# EMG_schemqtic.net
KiCad netlist of a schematic drawn in Altium Designer
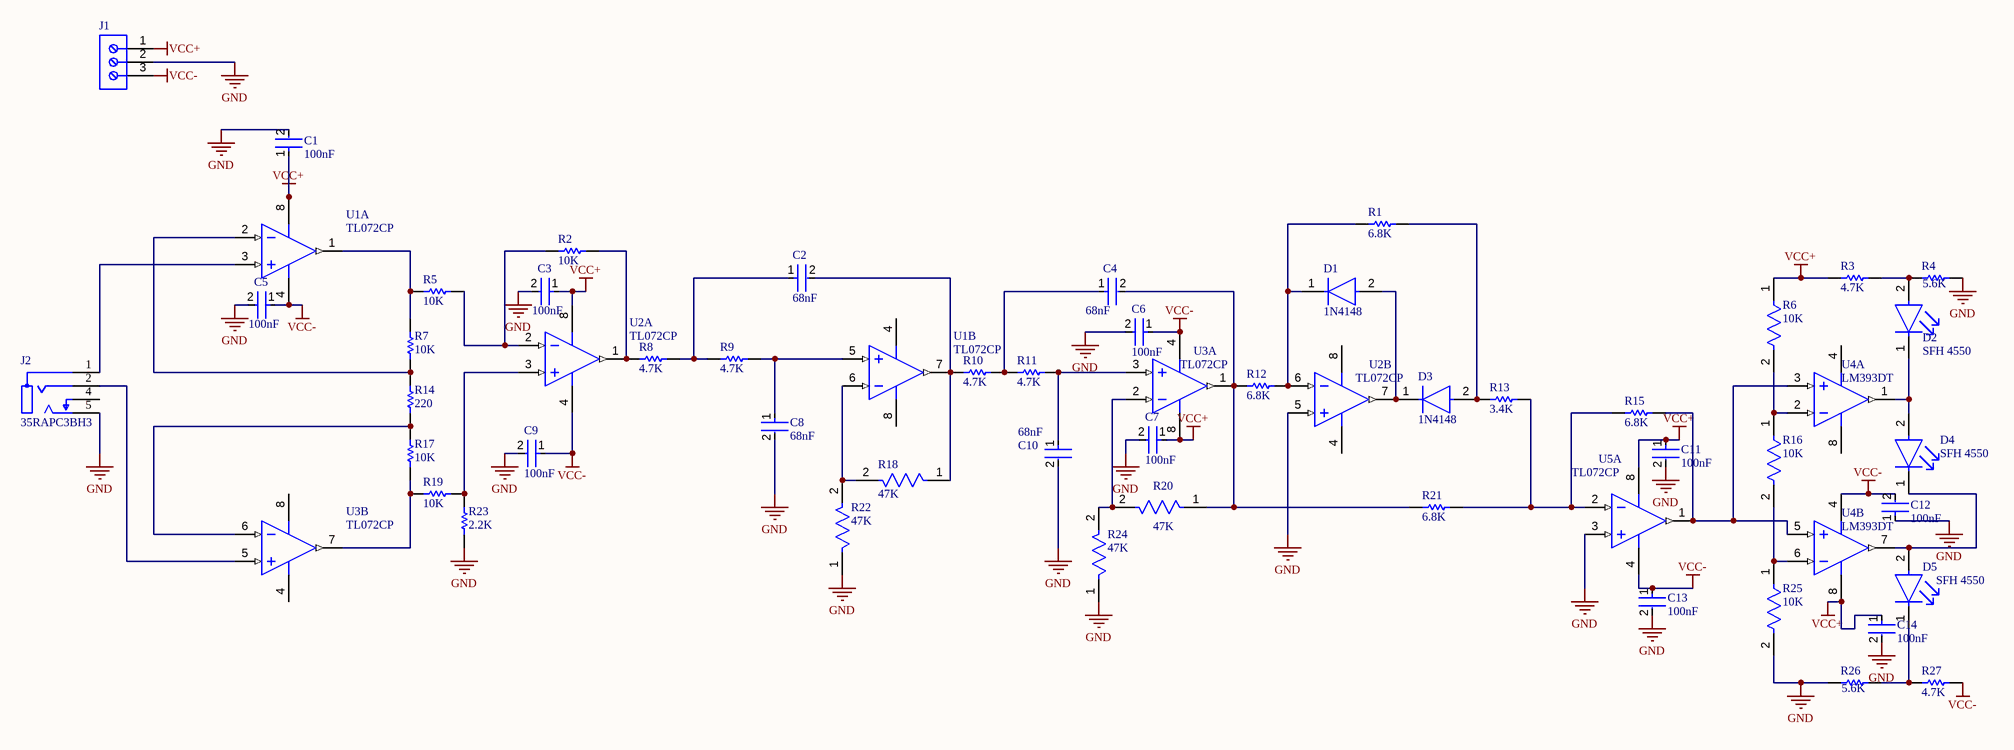
[diagram p0: EMG_schemqtic.SchDoc]

(export (version "E")
  (design (tool "Eeschema 10.0.6"))
  (components
    (comp (ref "C1")
      (value "100nF")
      (footprint "FP-CGA3E-0_3-0_1-IPC_A")
      (description "Cap Ceramic 100nF 50V X7R 10% Pad SMD 0603 +125°C Automotive T/R")
      (fields (field (name "TOLERANCE") "10%") (field (name "VOLTAGE") "50V"))
      (libsource (lib "Altium Content Vault") (part "b4654b650e69147ec39a6b967a45e02"))
    )
    (comp (ref "C2")
      (value "68nF")
      (footprint "FP-1206-L_3_2_0_2-W_1_6_0-IPC_A")
      (description "General Purpose Ceramic Capacitor, 1206, 68nF, 10%, X7R, 15%, 100V")
      (fields (field (name "VOLTAGE") "100V") (field (name "TOLERANCE") "10%"))
      (libsource (lib "Altium Content Vault") (part "02cd4be3c70576c341d710602a673aa"))
    )
    (comp (ref "C3")
      (value "100nF")
      (footprint "FP-CGA3E-0_3-0_1-IPC_A")
      (description "Cap Ceramic 100nF 50V X7R 10% Pad SMD 0603 +125°C Automotive T/R")
      (fields (field (name "TOLERANCE") "10%") (field (name "VOLTAGE") "50V"))
      (libsource (lib "Altium Content Vault") (part "b4654b650e69147ec39a6b967a45e02"))
    )
    (comp (ref "C4")
      (value "68nF")
      (footprint "FP-1206-L_3_2_0_2-W_1_6_0-IPC_A")
      (description "General Purpose Ceramic Capacitor, 1206, 68nF, 10%, X7R, 15%, 100V")
      (fields (field (name "VOLTAGE") "100V") (field (name "TOLERANCE") "10%"))
      (libsource (lib "Altium Content Vault") (part "02cd4be3c70576c341d710602a673aa"))
    )
    (comp (ref "C5")
      (value "100nF")
      (footprint "FP-CGA3E-0_3-0_1-IPC_A")
      (description "Cap Ceramic 100nF 50V X7R 10% Pad SMD 0603 +125°C Automotive T/R")
      (fields (field (name "TOLERANCE") "10%") (field (name "VOLTAGE") "50V"))
      (libsource (lib "Altium Content Vault") (part "b4654b650e69147ec39a6b967a45e02"))
    )
    (comp (ref "C6")
      (value "100nF")
      (footprint "FP-CGA3E-0_3-0_1-IPC_A")
      (description "Cap Ceramic 100nF 50V X7R 10% Pad SMD 0603 +125°C Automotive T/R")
      (fields (field (name "TOLERANCE") "10%") (field (name "VOLTAGE") "50V"))
      (libsource (lib "Altium Content Vault") (part "b4654b650e69147ec39a6b967a45e02"))
    )
    (comp (ref "C7")
      (value "100nF")
      (footprint "FP-CGA3E-0_3-0_1-IPC_A")
      (description "Cap Ceramic 100nF 50V X7R 10% Pad SMD 0603 +125°C Automotive T/R")
      (fields (field (name "TOLERANCE") "10%") (field (name "VOLTAGE") "50V"))
      (libsource (lib "Altium Content Vault") (part "b4654b650e69147ec39a6b967a45e02"))
    )
    (comp (ref "C8")
      (value "68nF")
      (footprint "FP-1206-L_3_2_0_2-W_1_6_0-IPC_A")
      (description "General Purpose Ceramic Capacitor, 1206, 68nF, 10%, X7R, 15%, 100V")
      (fields (field (name "VOLTAGE") "100V") (field (name "TOLERANCE") "10%"))
      (libsource (lib "Altium Content Vault") (part "02cd4be3c70576c341d710602a673aa"))
    )
    (comp (ref "C9")
      (value "100nF")
      (footprint "FP-CGA3E-0_3-0_1-IPC_A")
      (description "Cap Ceramic 100nF 50V X7R 10% Pad SMD 0603 +125°C Automotive T/R")
      (fields (field (name "TOLERANCE") "10%") (field (name "VOLTAGE") "50V"))
      (libsource (lib "Altium Content Vault") (part "b4654b650e69147ec39a6b967a45e02"))
    )
    (comp (ref "C10")
      (value "68nF")
      (footprint "FP-1206-L_3_2_0_2-W_1_6_0-IPC_A")
      (description "General Purpose Ceramic Capacitor, 1206, 68nF, 10%, X7R, 15%, 100V")
      (fields (field (name "VOLTAGE") "100V") (field (name "TOLERANCE") "10%"))
      (libsource (lib "Altium Content Vault") (part "02cd4be3c70576c341d710602a673aa"))
    )
    (comp (ref "C11")
      (value "100nF")
      (footprint "FP-CGA3E-0_3-0_1-IPC_A")
      (description "Cap Ceramic 100nF 50V X7R 10% Pad SMD 0603 +125°C Automotive T/R")
      (fields (field (name "TOLERANCE") "10%") (field (name "VOLTAGE") "50V"))
      (libsource (lib "Altium Content Vault") (part "b4654b650e69147ec39a6b967a45e02"))
    )
    (comp (ref "C12")
      (value "100nF")
      (footprint "FP-CGA3E-0_3-0_1-IPC_A")
      (description "Cap Ceramic 100nF 50V X7R 10% Pad SMD 0603 +125°C Automotive T/R")
      (fields (field (name "TOLERANCE") "10%") (field (name "VOLTAGE") "50V"))
      (libsource (lib "Altium Content Vault") (part "b4654b650e69147ec39a6b967a45e02"))
    )
    (comp (ref "C13")
      (value "100nF")
      (footprint "FP-CGA3E-0_3-0_1-IPC_A")
      (description "Cap Ceramic 100nF 50V X7R 10% Pad SMD 0603 +125°C Automotive T/R")
      (fields (field (name "TOLERANCE") "10%") (field (name "VOLTAGE") "50V"))
      (libsource (lib "Altium Content Vault") (part "b4654b650e69147ec39a6b967a45e02"))
    )
    (comp (ref "C14")
      (value "100nF")
      (footprint "FP-CGA3E-0_3-0_1-IPC_A")
      (description "Cap Ceramic 100nF 50V X7R 10% Pad SMD 0603 +125°C Automotive T/R")
      (fields (field (name "TOLERANCE") "10%") (field (name "VOLTAGE") "50V"))
      (libsource (lib "Altium Content Vault") (part "b4654b650e69147ec39a6b967a45e02"))
    )
    (comp (ref "D1")
      (value "1N4148")
      (footprint "FP-017AG-MFG")
      (description "DIODE GEN PURP 100V 200MA DO35")
      (fields (field (name "VOLTAGE") "100V"))
      (libsource (lib "Altium Content Vault") (part "d7152d700b627762746794eb795d46e"))
    )
    (comp (ref "D2")
      (value "SFH 4550")
      (footprint "FP-SFH_4550-MFG")
      (description "EMITTER IR 860NM 100MA RADIAL")
      (fields
        (field (name "OCTOPART") "https://octopart.com/sfh+4550-osram+opto-55410894")
        (field (name "MANUFACTURER") "Osram Opto")
      )
      (libsource (lib "Altium Content Vault") (part "75a0115997dd6a71327e26aab64f6f8"))
    )
    (comp (ref "D3")
      (value "1N4148")
      (footprint "FP-017AG-MFG")
      (description "DIODE GEN PURP 100V 200MA DO35")
      (fields (field (name "VOLTAGE") "100V"))
      (libsource (lib "Altium Content Vault") (part "d7152d700b627762746794eb795d46e"))
    )
    (comp (ref "D4")
      (value "SFH 4550")
      (footprint "FP-SFH_4550-MFG")
      (description "EMITTER IR 860NM 100MA RADIAL")
      (fields
        (field (name "OCTOPART") "https://octopart.com/sfh+4550-osram+opto-55410894")
        (field (name "MANUFACTURER") "Osram Opto")
      )
      (libsource (lib "Altium Content Vault") (part "75a0115997dd6a71327e26aab64f6f8"))
    )
    (comp (ref "D5")
      (value "SFH 4550")
      (footprint "FP-SFH_4550-MFG")
      (description "EMITTER IR 860NM 100MA RADIAL")
      (fields
        (field (name "OCTOPART") "https://octopart.com/sfh+4550-osram+opto-55410894")
        (field (name "MANUFACTURER") "Osram Opto")
      )
      (libsource (lib "Altium Content Vault") (part "75a0115997dd6a71327e26aab64f6f8"))
    )
    (comp (ref "J1")
      (value "691709710303")
      (footprint "691709710303")
      (description "Battery connector")
      (fields (field (name "VOLTAGE") "300V"))
      (libsource (lib "Altium Content Vault") (part "TBL - 1R - 03P - Screw"))
    )
    (comp (ref "J2")
      (value "35RAPC3BH3")
      (footprint "FP-35RAPC3BH3-MFG")
      (description "CONN JACK STEREO 3.5MM R/A")
      (libsource (lib "Altium Content Vault") (part "6593a1246df2d7246a2ad7da18ee256"))
    )
    (comp (ref "R1")
      (value "6.8K")
      (footprint "RESC1609X50X30LL10T20")
      (fields (field (name "PART NUMBER") "CRCW06036K80FKEA") (field (name "MANUFACTURER") "Vishay Dale"))
      (libsource (lib "Altium Content Vault") (part "RES"))
    )
    (comp (ref "R2")
      (value "10K")
      (footprint "RESC1609X50X30NL8T20")
      (description "Chip Resistor, 10 KOhm, +/- 1%, 100 mW, -55 to 155 degC, 0603 (1608 Metric), RoHS, Tape and Reel")
      (fields (field (name "MANUFACTURER") "Vishay Semiconductor"))
      (libsource (lib "Altium Content Vault") (part "RES-2"))
    )
    (comp (ref "R3")
      (value "4.7K")
      (footprint "RESC2013X70X40NL20T20")
      (description "Chip Resistor, 4.7 KOhm, +/- 1%, 0.125 W, -55 to 155 degC, 0805 (2012 Metric), RoHS, Tape and Reel")
      (fields (field (name "MANUFACTURER") "Panasonic"))
      (libsource (lib "Altium Content Vault") (part "RES-2"))
    )
    (comp (ref "R4")
      (value "5.6K")
      (footprint "RESC1005X40X25LL05T05")
      (fields (field (name "MANUFACTURER") "Vishay Dale") (field (name "PART NUMBER") "CRCW04025K60FKED"))
      (libsource (lib "Altium Content Vault") (part "RES"))
    )
    (comp (ref "R5")
      (value "10K")
      (footprint "RESC1609X50X30NL8T20")
      (description "Chip Resistor, 10 KOhm, +/- 1%, 100 mW, -55 to 155 degC, 0603 (1608 Metric), RoHS, Tape and Reel")
      (fields (field (name "MANUFACTURER") "Vishay Semiconductor"))
      (libsource (lib "Altium Content Vault") (part "RES-2"))
    )
    (comp (ref "R6")
      (value "10K")
      (footprint "FP-MCT0603-IPC_C")
      (description "RES SMD 100 OHM 1% 1/8W 0603")
      (fields (field (name "TOLERANCE") "1%"))
      (libsource (lib "Altium Content Vault") (part "1029c3af85768c4190bb7ad29bc67b5"))
    )
    (comp (ref "R7")
      (value "10K")
      (footprint "RESC1609X50X30NL8T20")
      (description "Chip Resistor, 10 KOhm, +/- 1%, 100 mW, -55 to 155 degC, 0603 (1608 Metric), RoHS, Tape and Reel")
      (fields (field (name "MANUFACTURER") "Vishay Semiconductor"))
      (libsource (lib "Altium Content Vault") (part "RES-2"))
    )
    (comp (ref "R8")
      (value "4.7K")
      (footprint "RESC1005X40X25LL05T05")
      (description "Chip Resistor, 4.7 KOhm, +/- 1%, 0.1 W, -55 to 155 degC, 0402 (1005 Metric), RoHS, Tape and Reel")
      (fields (field (name "TOLERANCE") "1%") (field (name "PARTNUMBER") "ERJ-2RKF4701X"))
      (libsource (lib "Altium Content Vault") (part "RES-2"))
    )
    (comp (ref "R9")
      (value "4.7K")
      (footprint "RESC1005X40X25LL05T05")
      (description "Chip Resistor, 4.7 KOhm, +/- 1%, 0.1 W, -55 to 155 degC, 0402 (1005 Metric), RoHS, Tape and Reel")
      (fields (field (name "TOLERANCE") "1%") (field (name "PARTNUMBER") "ERJ-2RKF4701X"))
      (libsource (lib "Altium Content Vault") (part "RES-2"))
    )
    (comp (ref "R10")
      (value "4.7K")
      (footprint "RESC1005X40X25LL05T05")
      (description "Chip Resistor, 4.7 KOhm, +/- 1%, 0.1 W, -55 to 155 degC, 0402 (1005 Metric), RoHS, Tape and Reel")
      (fields (field (name "TOLERANCE") "1%") (field (name "PARTNUMBER") "ERJ-2RKF4701X"))
      (libsource (lib "Altium Content Vault") (part "RES-2"))
    )
    (comp (ref "R11")
      (value "4.7K")
      (footprint "RESC1005X40X25LL05T05")
      (description "Chip Resistor, 4.7 KOhm, +/- 1%, 0.1 W, -55 to 155 degC, 0402 (1005 Metric), RoHS, Tape and Reel")
      (fields (field (name "TOLERANCE") "1%") (field (name "PARTNUMBER") "ERJ-2RKF4701X"))
      (libsource (lib "Altium Content Vault") (part "RES-2"))
    )
    (comp (ref "R12")
      (value "6.8K")
      (footprint "RESC1609X50X30LL10T20")
      (fields (field (name "PART NUMBER") "CRCW06036K80FKEA") (field (name "MANUFACTURER") "Vishay Dale"))
      (libsource (lib "Altium Content Vault") (part "RES"))
    )
    (comp (ref "R13")
      (value "3.4K")
      (footprint "RESC1609X50X30LL10T20")
      (fields (field (name "MANUFACTURER") "Vishay Dale") (field (name "PART NUMBER") "CRCW06033K40FKEA"))
      (libsource (lib "Altium Content Vault") (part "RES"))
    )
    (comp (ref "R14")
      (value "220")
      (footprint "RESC2013X70X40NL20T20")
      (fields (field (name "PART NUMBER") "ERJ6ENF2200V") (field (name "MANUFACTURER") "Panasonic"))
      (libsource (lib "Altium Content Vault") (part "RES"))
    )
    (comp (ref "R15")
      (value "6.8K")
      (footprint "RESC1609X50X30LL10T20")
      (fields (field (name "PART NUMBER") "CRCW06036K80FKEA") (field (name "MANUFACTURER") "Vishay Dale"))
      (libsource (lib "Altium Content Vault") (part "RES"))
    )
    (comp (ref "R16")
      (value "10K")
      (footprint "FP-MCT0603-IPC_C")
      (description "RES SMD 100 OHM 1% 1/8W 0603")
      (fields (field (name "TOLERANCE") "1%"))
      (libsource (lib "Altium Content Vault") (part "1029c3af85768c4190bb7ad29bc67b5"))
    )
    (comp (ref "R17")
      (value "10K")
      (footprint "RESC1609X50X30NL8T20")
      (description "Chip Resistor, 10 KOhm, +/- 1%, 100 mW, -55 to 155 degC, 0603 (1608 Metric), RoHS, Tape and Reel")
      (fields (field (name "MANUFACTURER") "Vishay Semiconductor"))
      (libsource (lib "Altium Content Vault") (part "RES-2"))
    )
    (comp (ref "R18")
      (value "47K")
      (footprint "FP-CRCW0603-e3-IPC_B")
      (description "RES SMD 47K OHM 1% 1/10W 0603")
      (fields (field (name "TOLERANCE") "1%"))
      (libsource (lib "Altium Content Vault") (part "1029c3af85768c4190bb7ad29bc67b5"))
    )
    (comp (ref "R19")
      (value "10K")
      (footprint "RESC1609X50X30NL8T20")
      (description "Chip Resistor, 10 KOhm, +/- 1%, 100 mW, -55 to 155 degC, 0603 (1608 Metric), RoHS, Tape and Reel")
      (fields (field (name "MANUFACTURER") "Vishay Semiconductor"))
      (libsource (lib "Altium Content Vault") (part "RES-2"))
    )
    (comp (ref "R20")
      (value "47K")
      (footprint "FP-CRCW0603-e3-IPC_B")
      (description "RES SMD 47K OHM 1% 1/10W 0603")
      (fields (field (name "TOLERANCE") "1%"))
      (libsource (lib "Altium Content Vault") (part "1029c3af85768c4190bb7ad29bc67b5"))
    )
    (comp (ref "R21")
      (value "6.8K")
      (footprint "RESC1609X50X30LL10T20")
      (fields (field (name "PART NUMBER") "CRCW06036K80FKEA") (field (name "MANUFACTURER") "Vishay Dale"))
      (libsource (lib "Altium Content Vault") (part "RES"))
    )
    (comp (ref "R22")
      (value "47K")
      (footprint "FP-CRCW0603-e3-IPC_B")
      (description "RES SMD 47K OHM 1% 1/10W 0603")
      (fields (field (name "TOLERANCE") "1%"))
      (libsource (lib "Altium Content Vault") (part "1029c3af85768c4190bb7ad29bc67b5"))
    )
    (comp (ref "R23")
      (value "2.2K")
      (footprint "RESC1608X55X25LL10T15")
      (fields (field (name "TOLERANCE") "1%") (field (name "MANUFACTURER") "Yageo"))
      (libsource (lib "Altium Content Vault") (part "RES-2"))
    )
    (comp (ref "R24")
      (value "47K")
      (footprint "FP-CRCW0603-e3-IPC_B")
      (description "RES SMD 47K OHM 1% 1/10W 0603")
      (fields (field (name "TOLERANCE") "1%"))
      (libsource (lib "Altium Content Vault") (part "1029c3af85768c4190bb7ad29bc67b5"))
    )
    (comp (ref "R25")
      (value "10K")
      (footprint "FP-MCT0603-IPC_C")
      (description "RES SMD 100 OHM 1% 1/8W 0603")
      (fields (field (name "TOLERANCE") "1%"))
      (libsource (lib "Altium Content Vault") (part "1029c3af85768c4190bb7ad29bc67b5"))
    )
    (comp (ref "R26")
      (value "5.6K")
      (footprint "RESC1005X40X25LL05T05")
      (fields (field (name "MANUFACTURER") "Vishay Dale") (field (name "PART NUMBER") "CRCW04025K60FKED"))
      (libsource (lib "Altium Content Vault") (part "RES"))
    )
    (comp (ref "R27")
      (value "4.7K")
      (footprint "RESC2013X70X40NL20T20")
      (description "Chip Resistor, 4.7 KOhm, +/- 1%, 0.125 W, -55 to 155 degC, 0805 (2012 Metric), RoHS, Tape and Reel")
      (fields (field (name "MANUFACTURER") "Panasonic"))
      (libsource (lib "Altium Content Vault") (part "RES-2"))
    )
    (comp (ref "U1")
      (value "TL072CP")
      (footprint "P0008A")
      (fields (field (name "MANUFACTURER") "Texas Instruments"))
      (libsource (lib "Altium Content Vault") (part "TI-AMP-D6-2-8_D"))
    )
    (comp (ref "U2")
      (value "TL072CP")
      (footprint "P0008A")
      (fields (field (name "MANUFACTURER") "Texas Instruments"))
      (libsource (lib "Altium Content Vault") (part "TI-AMP-D6-2-8_D"))
    )
    (comp (ref "U3")
      (value "TL072CP")
      (footprint "P0008A")
      (fields (field (name "MANUFACTURER") "Texas Instruments"))
      (libsource (lib "Altium Content Vault") (part "TI-AMP-D6-2-8_D"))
    )
    (comp (ref "U4")
      (value "LM393DT")
      (footprint "STM-SO-8_D_L")
      (description "Low-Power, Dual-Voltage Comparator, 2 to 36 V, 0 to 70 degC, 8-Pin SOIC (SO), RoHS, Tape and Reel")
      (fields (field (name "MANUFACTURER") "STMicroelectronics"))
      (libsource (lib "Altium Content Vault") (part "STM-LM393-SO8"))
    )
    (comp (ref "U5")
      (value "TL072CP")
      (footprint "P0008A")
      (fields (field (name "MANUFACTURER") "Texas Instruments"))
      (libsource (lib "Altium Content Vault") (part "TI-AMP-D6-2-8_D"))
    )
  )
  (nets
    (net (code "1") (name "GND") (class "Default")
      (node (ref "C1") (pin "2") (pinfunction "2_2") (pintype "passive"))
      (node (ref "C10") (pin "2") (pinfunction "2_2") (pintype "passive"))
      (node (ref "C11") (pin "2") (pinfunction "2_2") (pintype "passive"))
      (node (ref "C12") (pin "1") (pinfunction "1_1") (pintype "passive"))
      (node (ref "C13") (pin "2") (pinfunction "2_2") (pintype "passive"))
      (node (ref "C14") (pin "2") (pinfunction "2_2") (pintype "passive"))
      (node (ref "C3") (pin "2") (pinfunction "2_2") (pintype "passive"))
      (node (ref "C5") (pin "2") (pinfunction "2_2") (pintype "passive"))
      (node (ref "C6") (pin "2") (pinfunction "2_2") (pintype "passive"))
      (node (ref "C7") (pin "2") (pinfunction "2_2") (pintype "passive"))
      (node (ref "C8") (pin "2") (pinfunction "2_2") (pintype "passive"))
      (node (ref "C9") (pin "2") (pinfunction "2_2") (pintype "passive"))
      (node (ref "J1") (pin "2") (pinfunction "2_2") (pintype "passive"))
      (node (ref "J2") (pin "5") (pinfunction "5_5") (pintype "passive"))
      (node (ref "R22") (pin "1") (pinfunction "1_1") (pintype "passive"))
      (node (ref "R23") (pin "1") (pinfunction "1_1") (pintype "passive"))
      (node (ref "R24") (pin "1") (pinfunction "1_1") (pintype "passive"))
      (node (ref "R25") (pin "2") (pinfunction "2_2") (pintype "passive"))
      (node (ref "R26") (pin "1") (pinfunction "1_1") (pintype "passive"))
      (node (ref "R4") (pin "2") (pinfunction "2_2") (pintype "passive"))
      (node (ref "U2") (pin "5") (pinfunction "IN2+_5") (pintype "input"))
      (node (ref "U5") (pin "3") (pinfunction "IN1+_3") (pintype "input"))
    )
    (net (code "2") (name "Net-(C2-Pad1)") (class "Default")
      (node (ref "C2") (pin "1") (pinfunction "1_1") (pintype "passive"))
      (node (ref "R8") (pin "2") (pinfunction "2_2") (pintype "passive"))
      (node (ref "R9") (pin "1") (pinfunction "1_1") (pintype "passive"))
    )
    (net (code "3") (name "Net-(C4-Pad1)") (class "Default")
      (node (ref "C4") (pin "1") (pinfunction "1_1") (pintype "passive"))
      (node (ref "R10") (pin "2") (pinfunction "2_2") (pintype "passive"))
      (node (ref "R11") (pin "1") (pinfunction "1_1") (pintype "passive"))
    )
    (net (code "4") (name "Net-(D1-A)") (class "Default")
      (node (ref "D1") (pin "2") (pinfunction "A_2") (pintype "passive"))
      (node (ref "D3") (pin "1") (pinfunction "C_1") (pintype "passive"))
      (node (ref "U2") (pin "7") (pinfunction "OUT2_7") (pintype "output"))
    )
    (net (code "5") (name "Net-(D1-C)") (class "Default")
      (node (ref "D1") (pin "1") (pinfunction "C_1") (pintype "passive"))
      (node (ref "R1") (pin "1") (pinfunction "1_1") (pintype "passive"))
      (node (ref "R12") (pin "2") (pinfunction "2_2") (pintype "passive"))
      (node (ref "U2") (pin "6") (pinfunction "IN2-_6") (pintype "input"))
    )
    (net (code "6") (name "Net-(D2-A)") (class "Default")
      (node (ref "D2") (pin "2") (pinfunction "A_2") (pintype "passive"))
      (node (ref "R3") (pin "2") (pinfunction "2_2") (pintype "passive"))
      (node (ref "R4") (pin "1") (pinfunction "1_1") (pintype "passive"))
    )
    (net (code "7") (name "Net-(D2-C)") (class "Default")
      (node (ref "D2") (pin "1") (pinfunction "C_1") (pintype "passive"))
      (node (ref "D4") (pin "2") (pinfunction "A_2") (pintype "passive"))
      (node (ref "U4") (pin "1") (pinfunction "OUT1_1") (pintype "output"))
    )
    (net (code "8") (name "Net-(D3-A)") (class "Default")
      (node (ref "D3") (pin "2") (pinfunction "A_2") (pintype "passive"))
      (node (ref "R1") (pin "2") (pinfunction "2_2") (pintype "passive"))
      (node (ref "R13") (pin "1") (pinfunction "1_1") (pintype "passive"))
    )
    (net (code "9") (name "Net-(D4-C)") (class "Default")
      (node (ref "D4") (pin "1") (pinfunction "C_1") (pintype "passive"))
      (node (ref "D5") (pin "2") (pinfunction "A_2") (pintype "passive"))
      (node (ref "U4") (pin "7") (pinfunction "OUT2_7") (pintype "output"))
    )
    (net (code "10") (name "Net-(D5-C)") (class "Default")
      (node (ref "D5") (pin "1") (pinfunction "C_1") (pintype "passive"))
      (node (ref "R26") (pin "2") (pinfunction "2_2") (pintype "passive"))
      (node (ref "R27") (pin "1") (pinfunction "1_1") (pintype "passive"))
    )
    (net (code "11") (name "Net-(U1A-IN1+)") (class "Default")
      (node (ref "J2") (pin "1") (pinfunction "1_1") (pintype "passive"))
      (node (ref "U1") (pin "3") (pinfunction "IN1+_3") (pintype "input"))
    )
    (net (code "12") (name "Net-(U1A-IN1-)") (class "Default")
      (node (ref "R14") (pin "2") (pinfunction "2_2") (pintype "passive"))
      (node (ref "R7") (pin "1") (pinfunction "1_1") (pintype "passive"))
      (node (ref "U1") (pin "2") (pinfunction "IN1-_2") (pintype "input"))
    )
    (net (code "13") (name "Net-(U1A-OUT1)") (class "Default")
      (node (ref "R5") (pin "2") (pinfunction "2_2") (pintype "passive"))
      (node (ref "R7") (pin "2") (pinfunction "2_2") (pintype "passive"))
      (node (ref "U1") (pin "1") (pinfunction "OUT1_1") (pintype "output"))
    )
    (net (code "14") (name "Net-(U1B-IN2+)") (class "Default")
      (node (ref "C8") (pin "1") (pinfunction "1_1") (pintype "passive"))
      (node (ref "R9") (pin "2") (pinfunction "2_2") (pintype "passive"))
      (node (ref "U1") (pin "5") (pinfunction "IN2+_5") (pintype "input"))
    )
    (net (code "15") (name "Net-(U1B-IN2-)") (class "Default")
      (node (ref "R18") (pin "2") (pinfunction "2_2") (pintype "passive"))
      (node (ref "R22") (pin "2") (pinfunction "2_2") (pintype "passive"))
      (node (ref "U1") (pin "6") (pinfunction "IN2-_6") (pintype "input"))
    )
    (net (code "16") (name "Net-(U1B-OUT2)") (class "Default")
      (node (ref "C2") (pin "2") (pinfunction "2_2") (pintype "passive"))
      (node (ref "R10") (pin "1") (pinfunction "1_1") (pintype "passive"))
      (node (ref "R18") (pin "1") (pinfunction "1_1") (pintype "passive"))
      (node (ref "U1") (pin "7") (pinfunction "OUT2_7") (pintype "output"))
    )
    (net (code "17") (name "Net-(U2A-IN1+)") (class "Default")
      (node (ref "R19") (pin "1") (pinfunction "1_1") (pintype "passive"))
      (node (ref "R23") (pin "2") (pinfunction "2_2") (pintype "passive"))
      (node (ref "U2") (pin "3") (pinfunction "IN1+_3") (pintype "input"))
    )
    (net (code "18") (name "Net-(U2A-IN1-)") (class "Default")
      (node (ref "R2") (pin "2") (pinfunction "2_2") (pintype "passive"))
      (node (ref "R5") (pin "1") (pinfunction "1_1") (pintype "passive"))
      (node (ref "U2") (pin "2") (pinfunction "IN1-_2") (pintype "input"))
    )
    (net (code "19") (name "Net-(U2A-OUT1)") (class "Default")
      (node (ref "R2") (pin "1") (pinfunction "1_1") (pintype "passive"))
      (node (ref "R8") (pin "1") (pinfunction "1_1") (pintype "passive"))
      (node (ref "U2") (pin "1") (pinfunction "OUT1_1") (pintype "output"))
    )
    (net (code "20") (name "Net-(U3A-IN1+)") (class "Default")
      (node (ref "C10") (pin "1") (pinfunction "1_1") (pintype "passive"))
      (node (ref "R11") (pin "2") (pinfunction "2_2") (pintype "passive"))
      (node (ref "U3") (pin "3") (pinfunction "IN1+_3") (pintype "input"))
    )
    (net (code "21") (name "Net-(U3A-IN1-)") (class "Default")
      (node (ref "R20") (pin "2") (pinfunction "2_2") (pintype "passive"))
      (node (ref "R24") (pin "2") (pinfunction "2_2") (pintype "passive"))
      (node (ref "U3") (pin "2") (pinfunction "IN1-_2") (pintype "input"))
    )
    (net (code "22") (name "Net-(U3A-OUT1)") (class "Default")
      (node (ref "C4") (pin "2") (pinfunction "2_2") (pintype "passive"))
      (node (ref "R12") (pin "1") (pinfunction "1_1") (pintype "passive"))
      (node (ref "R20") (pin "1") (pinfunction "1_1") (pintype "passive"))
      (node (ref "R21") (pin "1") (pinfunction "1_1") (pintype "passive"))
      (node (ref "U3") (pin "1") (pinfunction "OUT1_1") (pintype "output"))
    )
    (net (code "23") (name "Net-(U3B-IN2+)") (class "Default")
      (node (ref "J2") (pin "2") (pinfunction "2_2") (pintype "passive"))
      (node (ref "U3") (pin "5") (pinfunction "IN2+_5") (pintype "input"))
    )
    (net (code "24") (name "Net-(U3B-IN2-)") (class "Default")
      (node (ref "R14") (pin "1") (pinfunction "1_1") (pintype "passive"))
      (node (ref "R17") (pin "2") (pinfunction "2_2") (pintype "passive"))
      (node (ref "U3") (pin "6") (pinfunction "IN2-_6") (pintype "input"))
    )
    (net (code "25") (name "Net-(U3B-OUT2)") (class "Default")
      (node (ref "R17") (pin "1") (pinfunction "1_1") (pintype "passive"))
      (node (ref "R19") (pin "2") (pinfunction "2_2") (pintype "passive"))
      (node (ref "U3") (pin "7") (pinfunction "OUT2_7") (pintype "output"))
    )
    (net (code "26") (name "Net-(U4A-IN1+)") (class "Default")
      (node (ref "R15") (pin "2") (pinfunction "2_2") (pintype "passive"))
      (node (ref "U4") (pin "3") (pinfunction "IN1+_3") (pintype "input"))
      (node (ref "U4") (pin "5") (pinfunction "IN2+_5") (pintype "input"))
      (node (ref "U5") (pin "1") (pinfunction "OUT1_1") (pintype "output"))
    )
    (net (code "27") (name "Net-(U4A-IN1-)") (class "Default")
      (node (ref "R16") (pin "1") (pinfunction "1_1") (pintype "passive"))
      (node (ref "R6") (pin "2") (pinfunction "2_2") (pintype "passive"))
      (node (ref "U4") (pin "2") (pinfunction "IN1-_2") (pintype "input"))
    )
    (net (code "28") (name "Net-(U4B-IN2-)") (class "Default")
      (node (ref "R16") (pin "2") (pinfunction "2_2") (pintype "passive"))
      (node (ref "R25") (pin "1") (pinfunction "1_1") (pintype "passive"))
      (node (ref "U4") (pin "6") (pinfunction "IN2-_6") (pintype "input"))
    )
    (net (code "29") (name "Net-(U5A-IN1-)") (class "Default")
      (node (ref "R13") (pin "2") (pinfunction "2_2") (pintype "passive"))
      (node (ref "R15") (pin "1") (pinfunction "1_1") (pintype "passive"))
      (node (ref "R21") (pin "2") (pinfunction "2_2") (pintype "passive"))
      (node (ref "U5") (pin "2") (pinfunction "IN1-_2") (pintype "input"))
    )
    (net (code "30") (name "VCC+") (class "Default")
      (node (ref "C1") (pin "1") (pinfunction "1_1") (pintype "passive"))
      (node (ref "C11") (pin "1") (pinfunction "1_1") (pintype "passive"))
      (node (ref "C14") (pin "1") (pinfunction "1_1") (pintype "passive"))
      (node (ref "C3") (pin "1") (pinfunction "1_1") (pintype "passive"))
      (node (ref "C7") (pin "1") (pinfunction "1_1") (pintype "passive"))
      (node (ref "J1") (pin "1") (pinfunction "1_1") (pintype "passive"))
      (node (ref "R3") (pin "1") (pinfunction "1_1") (pintype "passive"))
      (node (ref "R6") (pin "1") (pinfunction "1_1") (pintype "passive"))
      (node (ref "U1") (pin "8") (pinfunction "VCC+_8") (pintype "power_in"))
      (node (ref "U2") (pin "8") (pinfunction "VCC+_8") (pintype "power_in"))
      (node (ref "U3") (pin "8") (pinfunction "VCC+_8") (pintype "power_in"))
      (node (ref "U4") (pin "8") (pinfunction "VCC+_8") (pintype "power_in"))
      (node (ref "U5") (pin "8") (pinfunction "VCC+_8") (pintype "power_in"))
    )
    (net (code "31") (name "VCC-") (class "Default")
      (node (ref "C12") (pin "2") (pinfunction "2_2") (pintype "passive"))
      (node (ref "C13") (pin "1") (pinfunction "1_1") (pintype "passive"))
      (node (ref "C5") (pin "1") (pinfunction "1_1") (pintype "passive"))
      (node (ref "C6") (pin "1") (pinfunction "1_1") (pintype "passive"))
      (node (ref "C9") (pin "1") (pinfunction "1_1") (pintype "passive"))
      (node (ref "J1") (pin "3") (pinfunction "3_3") (pintype "passive"))
      (node (ref "R27") (pin "2") (pinfunction "2_2") (pintype "passive"))
      (node (ref "U1") (pin "4") (pinfunction "VCC-_4") (pintype "power_in"))
      (node (ref "U2") (pin "4") (pinfunction "VCC-_4") (pintype "power_in"))
      (node (ref "U3") (pin "4") (pinfunction "VCC-_4") (pintype "power_in"))
      (node (ref "U4") (pin "4") (pinfunction "VCC-_4") (pintype "power_in"))
      (node (ref "U5") (pin "4") (pinfunction "VCC-_4") (pintype "power_in"))
    )
    (net (code "32") (name "unconnected-(J2-Pad4)") (class "Default")
      (node (ref "J2") (pin "4") (pinfunction "4_4") (pintype "passive"))
    )
    (net (code "33") (name "unconnected-(U1B-VCC+-Pad8)") (class "Default")
      (node (ref "U1") (pin "8") (pinfunction "VCC+_8") (pintype "power_in"))
    )
    (net (code "34") (name "unconnected-(U1B-VCC--Pad4)") (class "Default")
      (node (ref "U1") (pin "4") (pinfunction "VCC-_4") (pintype "power_in"))
    )
    (net (code "35") (name "unconnected-(U2B-VCC+-Pad8)") (class "Default")
      (node (ref "U2") (pin "8") (pinfunction "VCC+_8") (pintype "power_in"))
    )
    (net (code "36") (name "unconnected-(U2B-VCC--Pad4)") (class "Default")
      (node (ref "U2") (pin "4") (pinfunction "VCC-_4") (pintype "power_in"))
    )
    (net (code "37") (name "unconnected-(U3B-VCC+-Pad8)") (class "Default")
      (node (ref "U3") (pin "8") (pinfunction "VCC+_8") (pintype "power_in"))
    )
    (net (code "38") (name "unconnected-(U3B-VCC--Pad4)") (class "Default")
      (node (ref "U3") (pin "4") (pinfunction "VCC-_4") (pintype "power_in"))
    )
    (net (code "39") (name "unconnected-(U4A-VCC+-Pad8)") (class "Default")
      (node (ref "U4") (pin "8") (pinfunction "VCC+_8") (pintype "power_in"))
    )
    (net (code "40") (name "unconnected-(U4A-VCC--Pad4)") (class "Default")
      (node (ref "U4") (pin "4") (pinfunction "VCC-_4") (pintype "power_in"))
    )
  )
)
